# 1-Schematic_LoRaRice_node3.net
KiCad netlist of a schematic drawn in EasyEDA
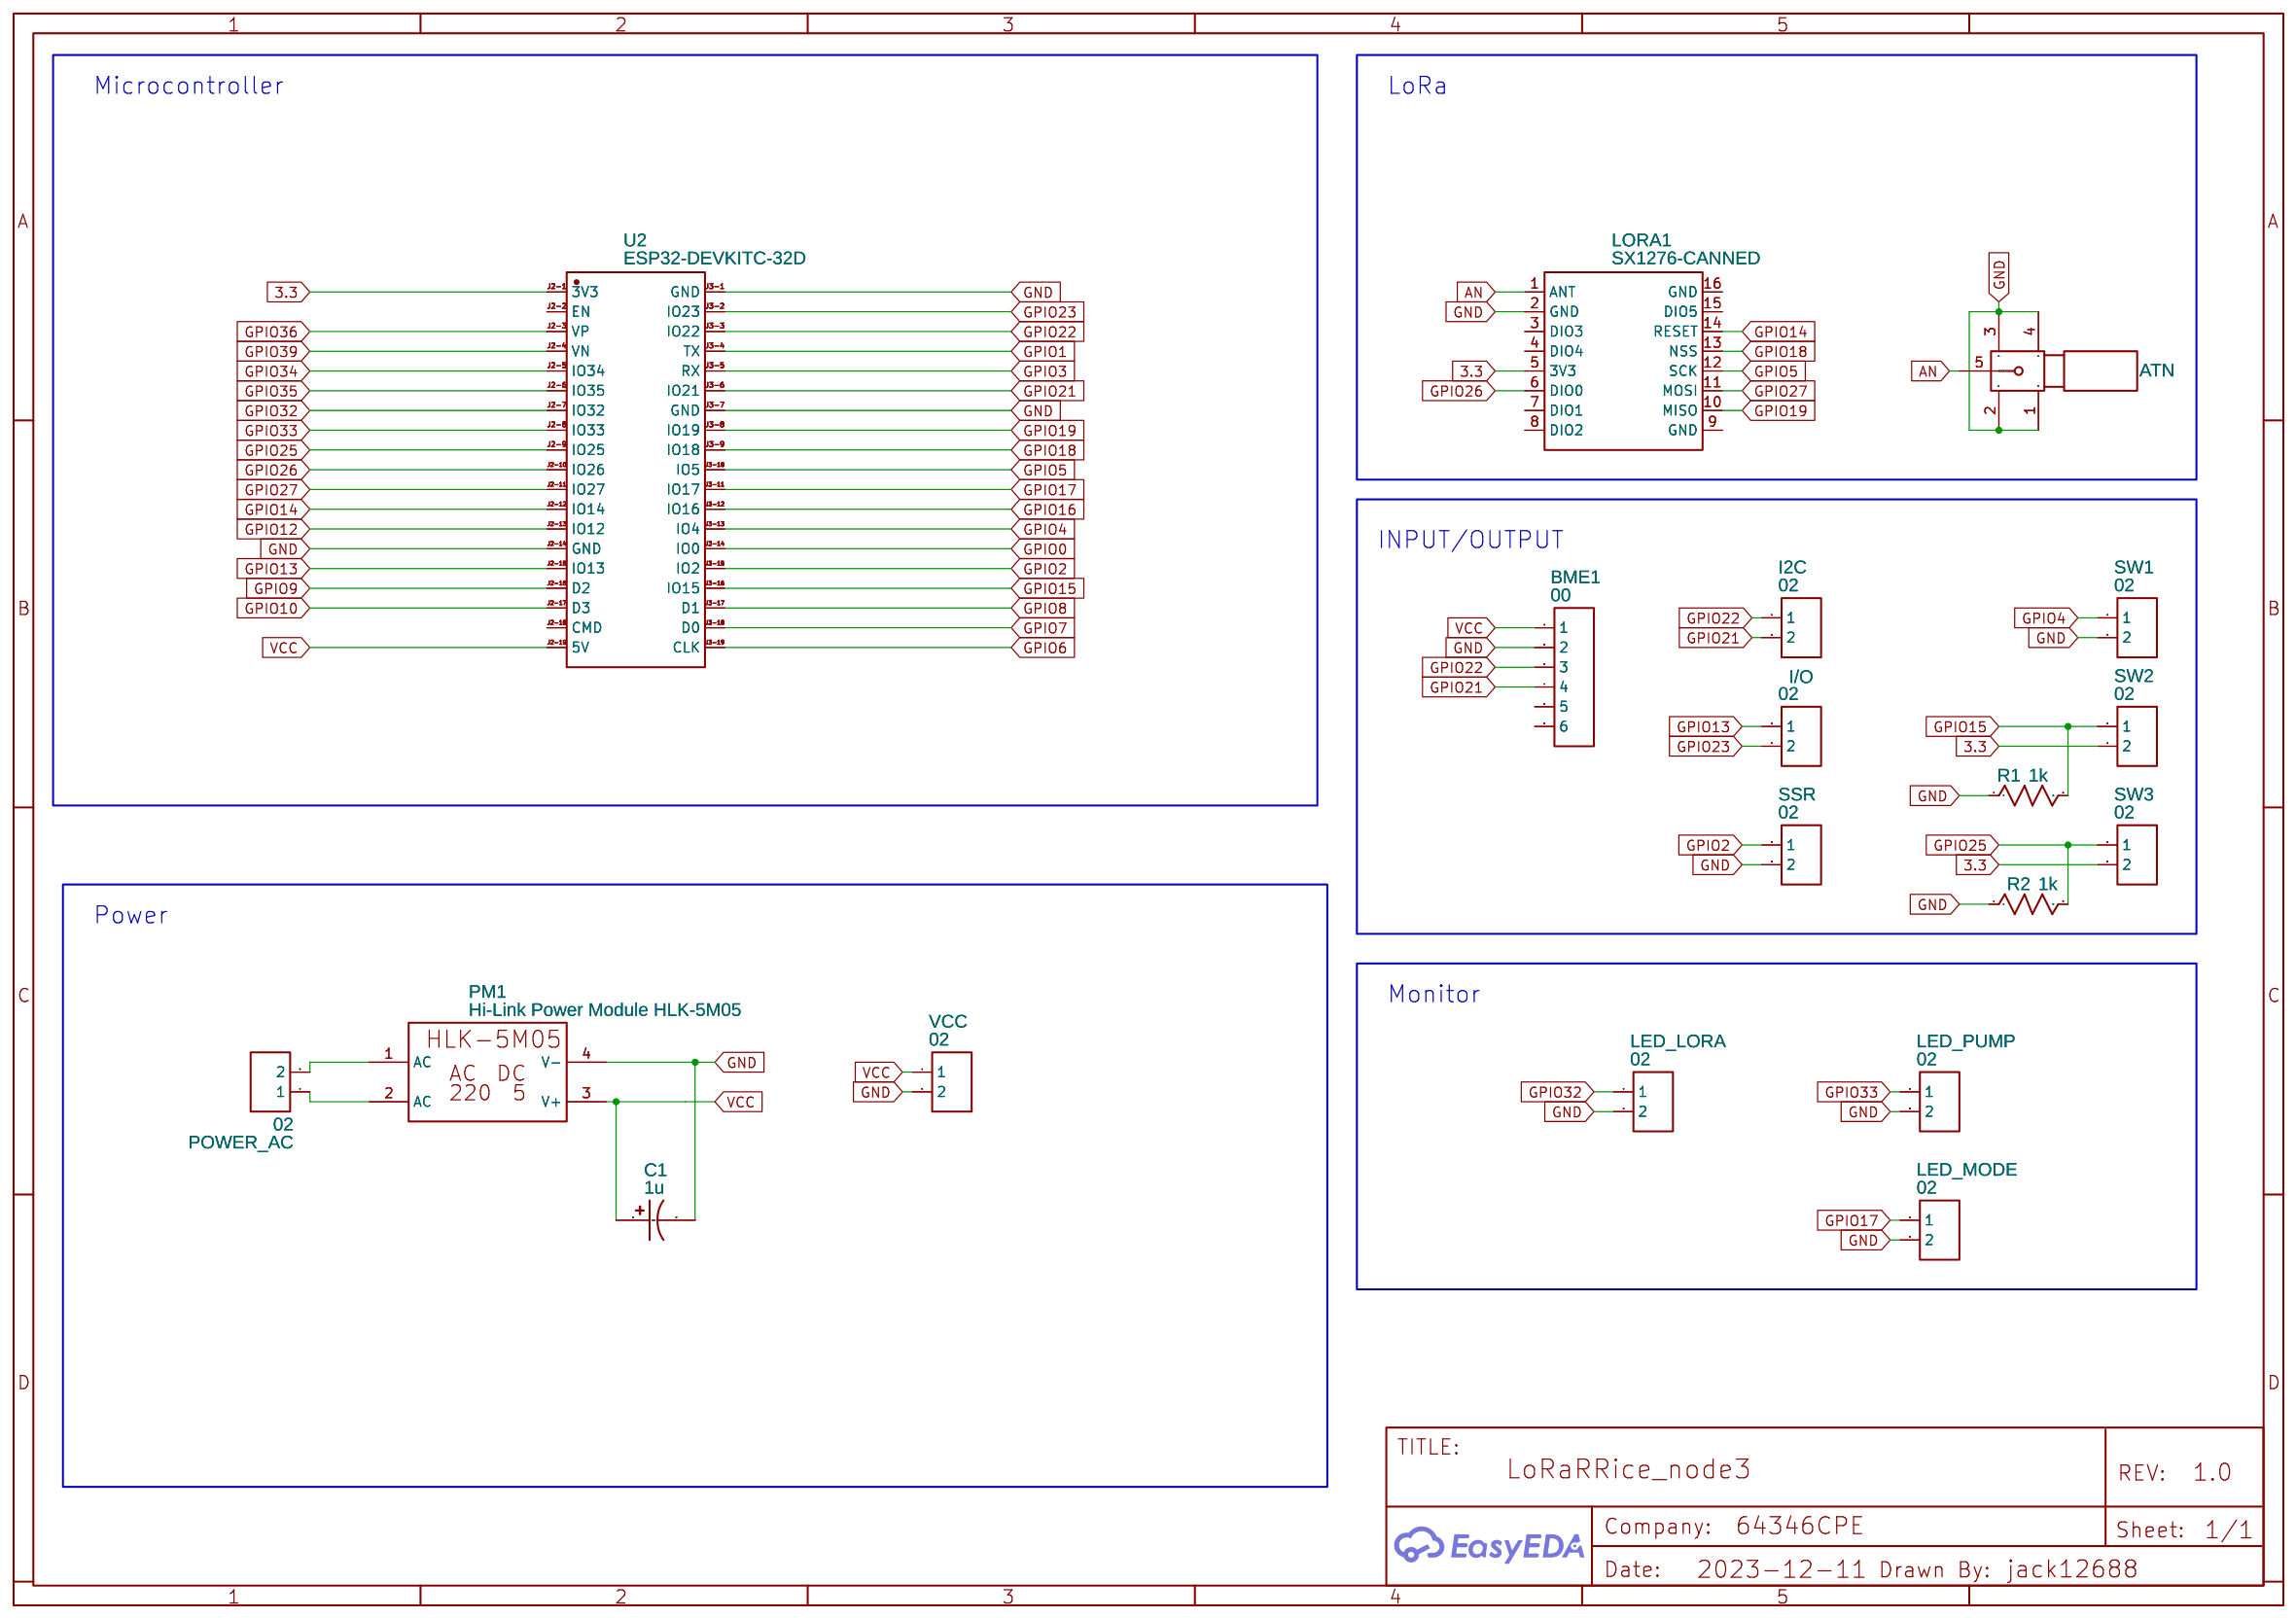
[diagram p0: schematic sheet]

(export (version "E")
  (design (tool "Eeschema 10.0.6"))
  (components
    (comp (ref "BME1") (value "00") (libsource (lib "") (part "HDR-F-2.54_1x6")))
    (comp (ref "C1") (value "1u") (libsource (lib "") (part "CE_TH_D4.0×F1.5_US")))
    (comp (ref "I/O") (value "02") (libsource (lib "") (part "CONN-TH_2P-P5.00_6")))
    (comp (ref "I2C") (value "02") (libsource (lib "") (part "CONN-TH_2P-P5.00_1")))
    (comp (ref "LED_LORA") (value "02") (libsource (lib "") (part "CONN-TH_2P-P5.00_8")))
    (comp (ref "LED_MODE") (value "02") (libsource (lib "") (part "CONN-TH_2P-P5.00_7")))
    (comp (ref "LED_PUMP") (value "02") (libsource (lib "") (part "CONN-TH_2P-P5.00_5")))
    (comp (ref "LORA1")
      (value "SX1276-CANNED")
      (fields (field (name "Manufacturer Part") "LoRa1276-C1") (field (name "Manufacturer") "G-NiceRF"))
      (libsource (lib "") (part "SX1276-CANNED"))
    )
    (comp (ref "PM1")
      (value "Hi-Link Power Module HLK-5M05")
      (fields (field (name "Manufacturer Part") "HLK-5M05") (field (name "Manufacturer") "Hi-Link"))
      (libsource (lib "") (part "Hi-Link Power Module HLK-5M05"))
    )
    (comp (ref "POWER_AC") (value "02") (libsource (lib "") (part "CONN-TH_2P-P5.00")))
    (comp (ref "R1") (value "1k") (libsource (lib "") (part "R_AXIAL-0.4_US")))
    (comp (ref "R2") (value "1k") (libsource (lib "") (part "R_AXIAL-0.4_US")))
    (comp (ref "RF1")
      (value "ATN")
      (fields
        (field (name "Manufacturer Part") "BWSMA-KE-P001")
        (field (name "Manufacturer") "BAT WIRELESS(蝙蝠无线)")
      )
      (libsource (lib "") (part "BWSMA-KE-P001"))
    )
    (comp (ref "SSR") (value "02") (libsource (lib "") (part "CONN-TH_2P-P5.00_3")))
    (comp (ref "SW1") (value "02") (libsource (lib "") (part "CONN-TH_2P-P5.00_4")))
    (comp (ref "SW2") (value "02") (libsource (lib "") (part "CONN-TH_2P-P5.00_4")))
    (comp (ref "SW3") (value "02") (libsource (lib "") (part "CONN-TH_2P-P5.00_4")))
    (comp (ref "U2")
      (value "ESP32-DEVKITC-32D")
      (fields
        (field (name "Manufacturer Part") "ESP32-DevKitC-32D")
        (field (name "Manufacturer") "ESPRESSIF(乐鑫)")
      )
      (libsource (lib "") (part "ESP32-DEVKITC-32D"))
    )
    (comp (ref "VCC") (value "02") (libsource (lib "") (part "CONN-TH_2P-P5.00_2")))
  )
  (nets
    (net (code "1") (name "3.3") (class "Default")
      (node (ref "LORA1") (pin "5") (pinfunction "3V3_5") (pintype "unspecified"))
      (node (ref "SW2") (pin "2") (pinfunction "2_2") (pintype "unspecified"))
      (node (ref "SW3") (pin "2") (pinfunction "2_2") (pintype "unspecified"))
      (node (ref "U2") (pin "J2-1") (pinfunction "3V3_J2-1") (pintype "unspecified"))
    )
    (net (code "2") (name "AN") (class "Default")
      (node (ref "LORA1") (pin "1") (pinfunction "ANT_1") (pintype "unspecified"))
      (node (ref "RF1") (pin "5") (pinfunction "5_5") (pintype "unspecified"))
    )
    (net (code "3") (name "GND") (class "Default")
      (node (ref "BME1") (pin "2") (pinfunction "2_2") (pintype "input"))
      (node (ref "C1") (pin "2") (pinfunction "2_2") (pintype "unspecified"))
      (node (ref "LED_LORA") (pin "2") (pinfunction "2_2") (pintype "unspecified"))
      (node (ref "LED_MODE") (pin "2") (pinfunction "2_2") (pintype "unspecified"))
      (node (ref "LED_PUMP") (pin "2") (pinfunction "2_2") (pintype "unspecified"))
      (node (ref "LORA1") (pin "2") (pinfunction "GND_2") (pintype "unspecified"))
      (node (ref "PM1") (pin "4") (pinfunction "V-_4") (pintype "unspecified"))
      (node (ref "R1") (pin "1") (pinfunction "1_1") (pintype "unspecified"))
      (node (ref "R2") (pin "1") (pinfunction "1_1") (pintype "unspecified"))
      (node (ref "RF1") (pin "1") (pinfunction "1_1") (pintype "unspecified"))
      (node (ref "RF1") (pin "2") (pinfunction "2_2") (pintype "unspecified"))
      (node (ref "RF1") (pin "3") (pinfunction "3_3") (pintype "unspecified"))
      (node (ref "RF1") (pin "4") (pinfunction "4_4") (pintype "unspecified"))
      (node (ref "SSR") (pin "2") (pinfunction "2_2") (pintype "unspecified"))
      (node (ref "SW1") (pin "2") (pinfunction "2_2") (pintype "unspecified"))
      (node (ref "U2") (pin "J2-14") (pinfunction "GND_J2-14") (pintype "unspecified"))
      (node (ref "U2") (pin "J3-1") (pinfunction "GND_J3-1") (pintype "unspecified"))
      (node (ref "U2") (pin "J3-7") (pinfunction "GND_J3-7") (pintype "unspecified"))
      (node (ref "VCC") (pin "2") (pinfunction "2_2") (pintype "unspecified"))
    )
    (net (code "4") (name "GPIO0") (class "Default")
      (node (ref "U2") (pin "J3-14") (pinfunction "IO0_J3-14") (pintype "unspecified"))
    )
    (net (code "5") (name "GPIO1") (class "Default")
      (node (ref "U2") (pin "J3-4") (pinfunction "TX_J3-4") (pintype "unspecified"))
    )
    (net (code "6") (name "GPIO2") (class "Default")
      (node (ref "SSR") (pin "1") (pinfunction "1_1") (pintype "unspecified"))
      (node (ref "U2") (pin "J3-15") (pinfunction "IO2_J3-15") (pintype "unspecified"))
    )
    (net (code "7") (name "GPIO3") (class "Default")
      (node (ref "U2") (pin "J3-5") (pinfunction "RX_J3-5") (pintype "unspecified"))
    )
    (net (code "8") (name "GPIO4") (class "Default")
      (node (ref "SW1") (pin "1") (pinfunction "1_1") (pintype "unspecified"))
      (node (ref "U2") (pin "J3-13") (pinfunction "IO4_J3-13") (pintype "unspecified"))
    )
    (net (code "9") (name "GPIO5") (class "Default")
      (node (ref "LORA1") (pin "12") (pinfunction "SCK_12") (pintype "unspecified"))
      (node (ref "U2") (pin "J3-10") (pinfunction "IO5_J3-10") (pintype "unspecified"))
    )
    (net (code "10") (name "GPIO6") (class "Default")
      (node (ref "U2") (pin "J3-19") (pinfunction "CLK_J3-19") (pintype "unspecified"))
    )
    (net (code "11") (name "GPIO7") (class "Default")
      (node (ref "U2") (pin "J3-18") (pinfunction "D0_J3-18") (pintype "unspecified"))
    )
    (net (code "12") (name "GPIO8") (class "Default")
      (node (ref "U2") (pin "J3-17") (pinfunction "D1_J3-17") (pintype "unspecified"))
    )
    (net (code "13") (name "GPIO9") (class "Default")
      (node (ref "U2") (pin "J2-16") (pinfunction "D2_J2-16") (pintype "unspecified"))
    )
    (net (code "14") (name "GPIO10") (class "Default")
      (node (ref "U2") (pin "J2-17") (pinfunction "D3_J2-17") (pintype "unspecified"))
    )
    (net (code "15") (name "GPIO12") (class "Default")
      (node (ref "U2") (pin "J2-13") (pinfunction "IO12_J2-13") (pintype "unspecified"))
    )
    (net (code "16") (name "GPIO13") (class "Default")
      (node (ref "I/O") (pin "1") (pinfunction "1_1") (pintype "unspecified"))
      (node (ref "U2") (pin "J2-15") (pinfunction "IO13_J2-15") (pintype "unspecified"))
    )
    (net (code "17") (name "GPIO14") (class "Default")
      (node (ref "LORA1") (pin "14") (pinfunction "RESET_14") (pintype "unspecified"))
      (node (ref "U2") (pin "J2-12") (pinfunction "IO14_J2-12") (pintype "unspecified"))
    )
    (net (code "18") (name "GPIO15") (class "Default")
      (node (ref "R1") (pin "2") (pinfunction "2_2") (pintype "unspecified"))
      (node (ref "SW2") (pin "1") (pinfunction "1_1") (pintype "unspecified"))
      (node (ref "U2") (pin "J3-16") (pinfunction "IO15_J3-16") (pintype "unspecified"))
    )
    (net (code "19") (name "GPIO16") (class "Default")
      (node (ref "U2") (pin "J3-12") (pinfunction "IO16_J3-12") (pintype "unspecified"))
    )
    (net (code "20") (name "GPIO17") (class "Default")
      (node (ref "LED_MODE") (pin "1") (pinfunction "1_1") (pintype "unspecified"))
      (node (ref "U2") (pin "J3-11") (pinfunction "IO17_J3-11") (pintype "unspecified"))
    )
    (net (code "21") (name "GPIO18") (class "Default")
      (node (ref "LORA1") (pin "13") (pinfunction "NSS_13") (pintype "unspecified"))
      (node (ref "U2") (pin "J3-9") (pinfunction "IO18_J3-9") (pintype "unspecified"))
    )
    (net (code "22") (name "GPIO19") (class "Default")
      (node (ref "LORA1") (pin "10") (pinfunction "MISO_10") (pintype "unspecified"))
      (node (ref "U2") (pin "J3-8") (pinfunction "IO19_J3-8") (pintype "unspecified"))
    )
    (net (code "23") (name "GPIO21") (class "Default")
      (node (ref "BME1") (pin "4") (pinfunction "4_4") (pintype "input"))
      (node (ref "I2C") (pin "2") (pinfunction "2_2") (pintype "unspecified"))
      (node (ref "U2") (pin "J3-6") (pinfunction "IO21_J3-6") (pintype "unspecified"))
    )
    (net (code "24") (name "GPIO22") (class "Default")
      (node (ref "BME1") (pin "3") (pinfunction "3_3") (pintype "input"))
      (node (ref "I2C") (pin "1") (pinfunction "1_1") (pintype "unspecified"))
      (node (ref "U2") (pin "J3-3") (pinfunction "IO22_J3-3") (pintype "unspecified"))
    )
    (net (code "25") (name "GPIO23") (class "Default")
      (node (ref "I/O") (pin "2") (pinfunction "2_2") (pintype "unspecified"))
      (node (ref "U2") (pin "J3-2") (pinfunction "IO23_J3-2") (pintype "unspecified"))
    )
    (net (code "26") (name "GPIO25") (class "Default")
      (node (ref "R2") (pin "2") (pinfunction "2_2") (pintype "unspecified"))
      (node (ref "SW3") (pin "1") (pinfunction "1_1") (pintype "unspecified"))
      (node (ref "U2") (pin "J2-9") (pinfunction "IO25_J2-9") (pintype "unspecified"))
    )
    (net (code "27") (name "GPIO26") (class "Default")
      (node (ref "LORA1") (pin "6") (pinfunction "DIO0_6") (pintype "unspecified"))
      (node (ref "U2") (pin "J2-10") (pinfunction "IO26_J2-10") (pintype "unspecified"))
    )
    (net (code "28") (name "GPIO27") (class "Default")
      (node (ref "LORA1") (pin "11") (pinfunction "MOSI_11") (pintype "unspecified"))
      (node (ref "U2") (pin "J2-11") (pinfunction "IO27_J2-11") (pintype "unspecified"))
    )
    (net (code "29") (name "GPIO32") (class "Default")
      (node (ref "LED_LORA") (pin "1") (pinfunction "1_1") (pintype "unspecified"))
      (node (ref "U2") (pin "J2-7") (pinfunction "IO32_J2-7") (pintype "unspecified"))
    )
    (net (code "30") (name "GPIO33") (class "Default")
      (node (ref "LED_PUMP") (pin "1") (pinfunction "1_1") (pintype "unspecified"))
      (node (ref "U2") (pin "J2-8") (pinfunction "IO33_J2-8") (pintype "unspecified"))
    )
    (net (code "31") (name "GPIO34") (class "Default")
      (node (ref "U2") (pin "J2-5") (pinfunction "IO34_J2-5") (pintype "unspecified"))
    )
    (net (code "32") (name "GPIO35") (class "Default")
      (node (ref "U2") (pin "J2-6") (pinfunction "IO35_J2-6") (pintype "unspecified"))
    )
    (net (code "33") (name "GPIO36") (class "Default")
      (node (ref "U2") (pin "J2-3") (pinfunction "VP_J2-3") (pintype "unspecified"))
    )
    (net (code "34") (name "GPIO39") (class "Default")
      (node (ref "U2") (pin "J2-4") (pinfunction "VN_J2-4") (pintype "unspecified"))
    )
    (net (code "35") (name "Net-(PM1-AC-Pad1)") (class "Default")
      (node (ref "PM1") (pin "1") (pinfunction "AC_1") (pintype "unspecified"))
      (node (ref "POWER_AC") (pin "2") (pinfunction "2_2") (pintype "unspecified"))
    )
    (net (code "36") (name "Net-(PM1-AC-Pad2)") (class "Default")
      (node (ref "PM1") (pin "2") (pinfunction "AC_2") (pintype "unspecified"))
      (node (ref "POWER_AC") (pin "1") (pinfunction "1_1") (pintype "unspecified"))
    )
    (net (code "37") (name "VCC") (class "Default")
      (node (ref "BME1") (pin "1") (pinfunction "1_1") (pintype "input"))
      (node (ref "C1") (pin "1") (pinfunction "1_1") (pintype "unspecified"))
      (node (ref "PM1") (pin "3") (pinfunction "V+_3") (pintype "unspecified"))
      (node (ref "U2") (pin "J2-19") (pinfunction "5V_J2-19") (pintype "unspecified"))
      (node (ref "VCC") (pin "1") (pinfunction "1_1") (pintype "unspecified"))
    )
    (net (code "38") (name "unconnected-(BME1-Pad5)") (class "Default")
      (node (ref "BME1") (pin "5") (pinfunction "5_5") (pintype "input"))
    )
    (net (code "39") (name "unconnected-(BME1-Pad6)") (class "Default")
      (node (ref "BME1") (pin "6") (pinfunction "6_6") (pintype "input"))
    )
    (net (code "40") (name "unconnected-(LORA1-DIO1-Pad7)") (class "Default")
      (node (ref "LORA1") (pin "7") (pinfunction "DIO1_7") (pintype "unspecified"))
    )
    (net (code "41") (name "unconnected-(LORA1-DIO2-Pad8)") (class "Default")
      (node (ref "LORA1") (pin "8") (pinfunction "DIO2_8") (pintype "unspecified"))
    )
    (net (code "42") (name "unconnected-(LORA1-DIO3-Pad3)") (class "Default")
      (node (ref "LORA1") (pin "3") (pinfunction "DIO3_3") (pintype "unspecified"))
    )
    (net (code "43") (name "unconnected-(LORA1-DIO4-Pad4)") (class "Default")
      (node (ref "LORA1") (pin "4") (pinfunction "DIO4_4") (pintype "unspecified"))
    )
    (net (code "44") (name "unconnected-(LORA1-DIO5-Pad15)") (class "Default")
      (node (ref "LORA1") (pin "15") (pinfunction "DIO5_15") (pintype "unspecified"))
    )
    (net (code "45") (name "unconnected-(LORA1-GND-Pad9)") (class "Default")
      (node (ref "LORA1") (pin "9") (pinfunction "GND_9") (pintype "unspecified"))
    )
    (net (code "46") (name "unconnected-(LORA1-GND-Pad16)") (class "Default")
      (node (ref "LORA1") (pin "16") (pinfunction "GND_16") (pintype "unspecified"))
    )
    (net (code "47") (name "unconnected-(U2-CMD-PadJ2-18)") (class "Default")
      (node (ref "U2") (pin "J2-18") (pinfunction "CMD_J2-18") (pintype "unspecified"))
    )
    (net (code "48") (name "unconnected-(U2-EN-PadJ2-2)") (class "Default")
      (node (ref "U2") (pin "J2-2") (pinfunction "EN_J2-2") (pintype "unspecified"))
    )
  )
)
